# Breakout_carrier_bittern.net
KiCad netlist of a schematic drawn in EAGLE
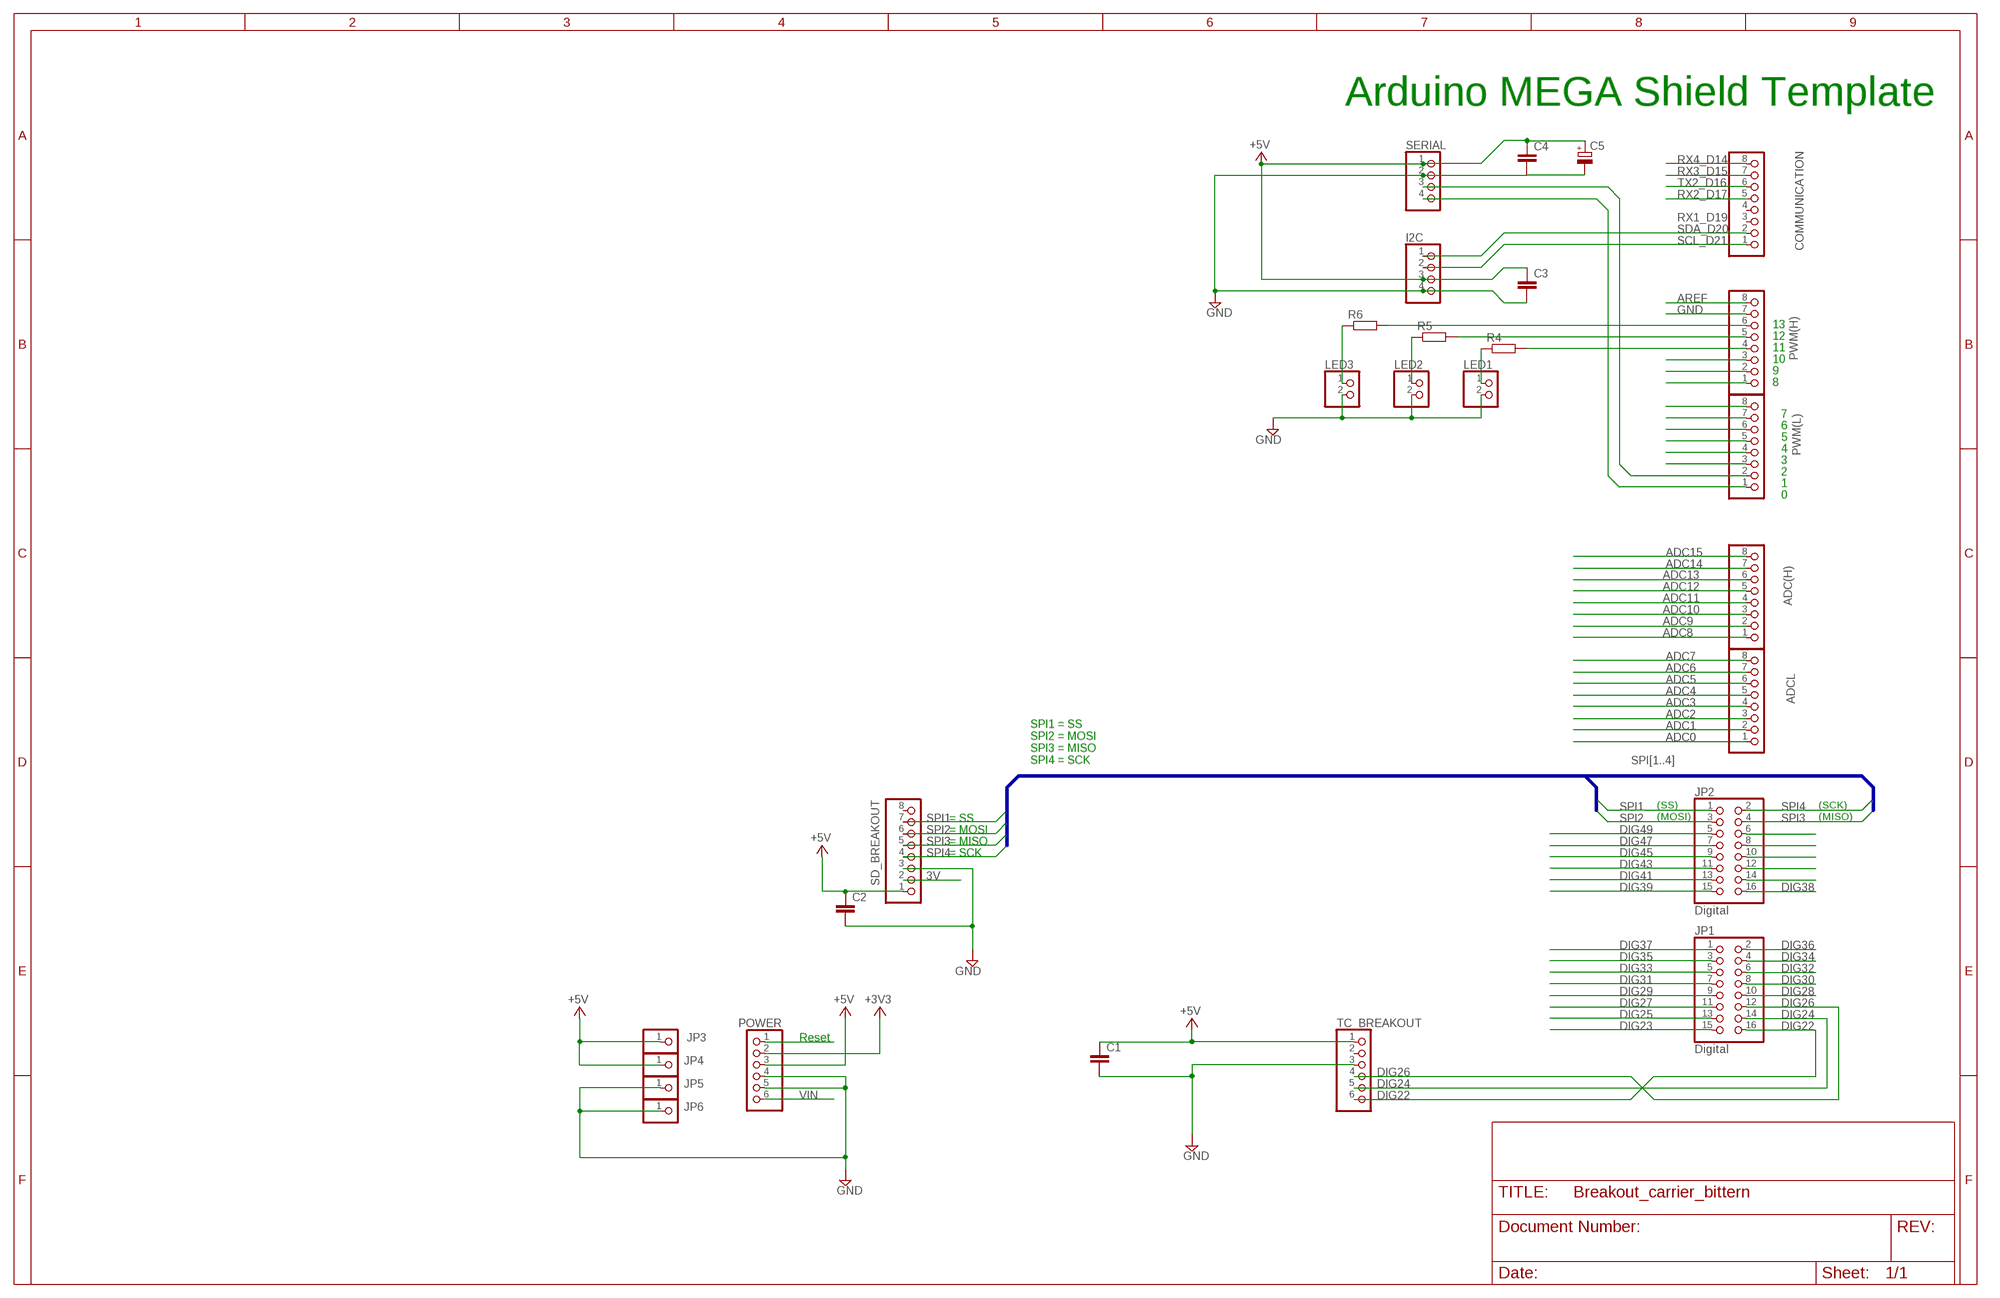
[diagram p0: schematic, sheet 1]

(export (version "E")
  (design (tool "Eeschema 10.0.6"))
  (components
    (comp (ref "ADC(H)")
      (value "PINHD-1X8")
      (footprint "eagle-import:1X08")
      (libsource (lib "eagle-import") (part "PINHD-1X8"))
    )
    (comp (ref "ADCL")
      (value "PINHD-1X8")
      (footprint "eagle-import:1X08")
      (libsource (lib "eagle-import") (part "PINHD-1X8"))
    )
    (comp (ref "C1")
      (value "C-EU050-045X075")
      (footprint "eagle-import:C050-045X075")
      (libsource (lib "eagle-import") (part "C-EU050-045X075"))
    )
    (comp (ref "C2")
      (value "C-EU050-045X075")
      (footprint "eagle-import:C050-045X075")
      (libsource (lib "eagle-import") (part "C-EU050-045X075"))
    )
    (comp (ref "C3")
      (value "C-EU050-045X075")
      (footprint "eagle-import:C050-045X075")
      (libsource (lib "eagle-import") (part "C-EU050-045X075"))
    )
    (comp (ref "C4")
      (value "C-EU050-045X075")
      (footprint "eagle-import:C050-045X075")
      (libsource (lib "eagle-import") (part "C-EU050-045X075"))
    )
    (comp (ref "C5")
      (value "CPOL-EUE2.5-6")
      (footprint "eagle-import:E2,5-6")
      (libsource (lib "eagle-import") (part "CPOL-EUE2.5-6"))
    )
    (comp (ref "COMMUNICATION")
      (value "PINHD-1X8")
      (footprint "eagle-import:1X08")
      (libsource (lib "eagle-import") (part "PINHD-1X8"))
    )
    (comp (ref "I2C")
      (value "PINHD-1X4")
      (footprint "eagle-import:1X04")
      (libsource (lib "eagle-import") (part "PINHD-1X4"))
    )
    (comp (ref "JP1")
      (value "Digital")
      (footprint "eagle-import:2X08")
      (libsource (lib "eagle-import") (part "PINHD-2X8"))
    )
    (comp (ref "JP2")
      (value "Digital")
      (footprint "eagle-import:2X08")
      (libsource (lib "eagle-import") (part "PINHD-2X8"))
    )
    (comp (ref "JP3")
      (value "PINHD-1X1")
      (footprint "eagle-import:1X01")
      (libsource (lib "eagle-import") (part "PINHD-1X1"))
    )
    (comp (ref "JP4")
      (value "PINHD-1X1")
      (footprint "eagle-import:1X01")
      (libsource (lib "eagle-import") (part "PINHD-1X1"))
    )
    (comp (ref "JP5")
      (value "PINHD-1X1")
      (footprint "eagle-import:1X01")
      (libsource (lib "eagle-import") (part "PINHD-1X1"))
    )
    (comp (ref "JP6")
      (value "PINHD-1X1")
      (footprint "eagle-import:1X01")
      (libsource (lib "eagle-import") (part "PINHD-1X1"))
    )
    (comp (ref "LED1")
      (value "PINHD-1X2")
      (footprint "eagle-import:1X02")
      (libsource (lib "eagle-import") (part "PINHD-1X2"))
    )
    (comp (ref "LED2")
      (value "PINHD-1X2")
      (footprint "eagle-import:1X02")
      (libsource (lib "eagle-import") (part "PINHD-1X2"))
    )
    (comp (ref "LED3")
      (value "PINHD-1X2")
      (footprint "eagle-import:1X02")
      (libsource (lib "eagle-import") (part "PINHD-1X2"))
    )
    (comp (ref "POWER")
      (value "PINHD-1X6")
      (footprint "eagle-import:1X06")
      (libsource (lib "eagle-import") (part "PINHD-1X6"))
    )
    (comp (ref "PWM(H)")
      (value "PINHD-1X8")
      (footprint "eagle-import:1X08")
      (libsource (lib "eagle-import") (part "PINHD-1X8"))
    )
    (comp (ref "PWM(L)")
      (value "PINHD-1X8")
      (footprint "eagle-import:1X08")
      (libsource (lib "eagle-import") (part "PINHD-1X8"))
    )
    (comp (ref "R4")
      (value "R-EU_0309/12")
      (footprint "eagle-import:0309_12")
      (libsource (lib "eagle-import") (part "R-EU_0309/12"))
    )
    (comp (ref "R5")
      (value "R-EU_0309/12")
      (footprint "eagle-import:0309_12")
      (libsource (lib "eagle-import") (part "R-EU_0309/12"))
    )
    (comp (ref "R6")
      (value "R-EU_0309/12")
      (footprint "eagle-import:0309_12")
      (libsource (lib "eagle-import") (part "R-EU_0309/12"))
    )
    (comp (ref "SD_BREAKOUT")
      (value "PINHD-1X8")
      (footprint "eagle-import:1X08")
      (libsource (lib "eagle-import") (part "PINHD-1X8"))
    )
    (comp (ref "SERIAL")
      (value "PINHD-1X4")
      (footprint "eagle-import:1X04")
      (libsource (lib "eagle-import") (part "PINHD-1X4"))
    )
    (comp (ref "TC_BREAKOUT")
      (value "PINHD-1X6")
      (footprint "eagle-import:1X06")
      (libsource (lib "eagle-import") (part "PINHD-1X6"))
    )
  )
  (nets
    (net (code "1") (name "+3V3") (class "Default")
      (node (ref "POWER") (pin "2") (pinfunction "2_2") (pintype "passive"))
    )
    (net (code "2") (name "+5V") (class "Default")
      (node (ref "C1") (pin "1") (pinfunction "1_1") (pintype "passive"))
      (node (ref "C2") (pin "1") (pinfunction "1_1") (pintype "passive"))
      (node (ref "C3") (pin "1") (pinfunction "1_1") (pintype "passive"))
      (node (ref "C4") (pin "1") (pinfunction "1_1") (pintype "passive"))
      (node (ref "C5") (pin "+") (pinfunction "+_+") (pintype "passive"))
      (node (ref "I2C") (pin "3") (pinfunction "3_3") (pintype "passive"))
      (node (ref "JP3") (pin "1") (pinfunction "1_1") (pintype "passive"))
      (node (ref "JP4") (pin "1") (pinfunction "1_1") (pintype "passive"))
      (node (ref "POWER") (pin "3") (pinfunction "3_3") (pintype "passive"))
      (node (ref "SD_BREAKOUT") (pin "1") (pinfunction "1_1") (pintype "passive"))
      (node (ref "SERIAL") (pin "1") (pinfunction "1_1") (pintype "passive"))
      (node (ref "TC_BREAKOUT") (pin "1") (pinfunction "1_1") (pintype "passive"))
    )
    (net (code "3") (name "/3V") (class "Default")
      (node (ref "SD_BREAKOUT") (pin "2") (pinfunction "2_2") (pintype "passive"))
    )
    (net (code "4") (name "/ADC0") (class "Default")
      (node (ref "ADCL") (pin "1") (pinfunction "1_1") (pintype "passive"))
    )
    (net (code "5") (name "/ADC1") (class "Default")
      (node (ref "ADCL") (pin "2") (pinfunction "2_2") (pintype "passive"))
    )
    (net (code "6") (name "/ADC2") (class "Default")
      (node (ref "ADCL") (pin "3") (pinfunction "3_3") (pintype "passive"))
    )
    (net (code "7") (name "/ADC3") (class "Default")
      (node (ref "ADCL") (pin "4") (pinfunction "4_4") (pintype "passive"))
    )
    (net (code "8") (name "/ADC4") (class "Default")
      (node (ref "ADCL") (pin "5") (pinfunction "5_5") (pintype "passive"))
    )
    (net (code "9") (name "/ADC5") (class "Default")
      (node (ref "ADCL") (pin "6") (pinfunction "6_6") (pintype "passive"))
    )
    (net (code "10") (name "/ADC6") (class "Default")
      (node (ref "ADCL") (pin "7") (pinfunction "7_7") (pintype "passive"))
    )
    (net (code "11") (name "/ADC7") (class "Default")
      (node (ref "ADCL") (pin "8") (pinfunction "8_8") (pintype "passive"))
    )
    (net (code "12") (name "/ADC8") (class "Default")
      (node (ref "ADC(H)") (pin "1") (pinfunction "1_1") (pintype "passive"))
    )
    (net (code "13") (name "/ADC9") (class "Default")
      (node (ref "ADC(H)") (pin "2") (pinfunction "2_2") (pintype "passive"))
    )
    (net (code "14") (name "/ADC10") (class "Default")
      (node (ref "ADC(H)") (pin "3") (pinfunction "3_3") (pintype "passive"))
    )
    (net (code "15") (name "/ADC11") (class "Default")
      (node (ref "ADC(H)") (pin "4") (pinfunction "4_4") (pintype "passive"))
    )
    (net (code "16") (name "/ADC12") (class "Default")
      (node (ref "ADC(H)") (pin "5") (pinfunction "5_5") (pintype "passive"))
    )
    (net (code "17") (name "/ADC13") (class "Default")
      (node (ref "ADC(H)") (pin "6") (pinfunction "6_6") (pintype "passive"))
    )
    (net (code "18") (name "/ADC14") (class "Default")
      (node (ref "ADC(H)") (pin "7") (pinfunction "7_7") (pintype "passive"))
    )
    (net (code "19") (name "/ADC15") (class "Default")
      (node (ref "ADC(H)") (pin "8") (pinfunction "8_8") (pintype "passive"))
    )
    (net (code "20") (name "/AREF") (class "Default")
      (node (ref "PWM(H)") (pin "8") (pinfunction "8_8") (pintype "passive"))
    )
    (net (code "21") (name "/DIG22") (class "Default")
      (node (ref "JP1") (pin "16") (pinfunction "16_16") (pintype "passive"))
      (node (ref "TC_BREAKOUT") (pin "6") (pinfunction "6_6") (pintype "passive"))
    )
    (net (code "22") (name "/DIG23") (class "Default")
      (node (ref "JP1") (pin "15") (pinfunction "15_15") (pintype "passive"))
    )
    (net (code "23") (name "/DIG24") (class "Default")
      (node (ref "JP1") (pin "14") (pinfunction "14_14") (pintype "passive"))
      (node (ref "TC_BREAKOUT") (pin "5") (pinfunction "5_5") (pintype "passive"))
    )
    (net (code "24") (name "/DIG25") (class "Default")
      (node (ref "JP1") (pin "13") (pinfunction "13_13") (pintype "passive"))
    )
    (net (code "25") (name "/DIG26") (class "Default")
      (node (ref "JP1") (pin "12") (pinfunction "12_12") (pintype "passive"))
      (node (ref "TC_BREAKOUT") (pin "4") (pinfunction "4_4") (pintype "passive"))
    )
    (net (code "26") (name "/DIG27") (class "Default")
      (node (ref "JP1") (pin "11") (pinfunction "11_11") (pintype "passive"))
    )
    (net (code "27") (name "/DIG28") (class "Default")
      (node (ref "JP1") (pin "10") (pinfunction "10_10") (pintype "passive"))
    )
    (net (code "28") (name "/DIG29") (class "Default")
      (node (ref "JP1") (pin "9") (pinfunction "9_9") (pintype "passive"))
    )
    (net (code "29") (name "/DIG30") (class "Default")
      (node (ref "JP1") (pin "8") (pinfunction "8_8") (pintype "passive"))
    )
    (net (code "30") (name "/DIG31") (class "Default")
      (node (ref "JP1") (pin "7") (pinfunction "7_7") (pintype "passive"))
    )
    (net (code "31") (name "/DIG32") (class "Default")
      (node (ref "JP1") (pin "6") (pinfunction "6_6") (pintype "passive"))
    )
    (net (code "32") (name "/DIG33") (class "Default")
      (node (ref "JP1") (pin "5") (pinfunction "5_5") (pintype "passive"))
    )
    (net (code "33") (name "/DIG34") (class "Default")
      (node (ref "JP1") (pin "4") (pinfunction "4_4") (pintype "passive"))
    )
    (net (code "34") (name "/DIG35") (class "Default")
      (node (ref "JP1") (pin "3") (pinfunction "3_3") (pintype "passive"))
    )
    (net (code "35") (name "/DIG36") (class "Default")
      (node (ref "JP1") (pin "2") (pinfunction "2_2") (pintype "passive"))
    )
    (net (code "36") (name "/DIG37") (class "Default")
      (node (ref "JP1") (pin "1") (pinfunction "1_1") (pintype "passive"))
    )
    (net (code "37") (name "/DIG38") (class "Default")
      (node (ref "JP2") (pin "16") (pinfunction "16_16") (pintype "passive"))
    )
    (net (code "38") (name "/DIG39") (class "Default")
      (node (ref "JP2") (pin "15") (pinfunction "15_15") (pintype "passive"))
    )
    (net (code "39") (name "/DIG41") (class "Default")
      (node (ref "JP2") (pin "13") (pinfunction "13_13") (pintype "passive"))
    )
    (net (code "40") (name "/DIG43") (class "Default")
      (node (ref "JP2") (pin "11") (pinfunction "11_11") (pintype "passive"))
    )
    (net (code "41") (name "/DIG45") (class "Default")
      (node (ref "JP2") (pin "9") (pinfunction "9_9") (pintype "passive"))
    )
    (net (code "42") (name "/DIG47") (class "Default")
      (node (ref "JP2") (pin "7") (pinfunction "7_7") (pintype "passive"))
    )
    (net (code "43") (name "/DIG49") (class "Default")
      (node (ref "JP2") (pin "5") (pinfunction "5_5") (pintype "passive"))
    )
    (net (code "44") (name "/RX1_D19") (class "Default")
      (node (ref "PWM(L)") (pin "1") (pinfunction "1_1") (pintype "passive"))
      (node (ref "SERIAL") (pin "4") (pinfunction "4_4") (pintype "passive"))
    )
    (net (code "45") (name "/RX2_D17") (class "Default")
      (node (ref "COMMUNICATION") (pin "5") (pinfunction "5_5") (pintype "passive"))
    )
    (net (code "46") (name "/RX3_D15") (class "Default")
      (node (ref "COMMUNICATION") (pin "7") (pinfunction "7_7") (pintype "passive"))
    )
    (net (code "47") (name "/RX4_D14") (class "Default")
      (node (ref "COMMUNICATION") (pin "8") (pinfunction "8_8") (pintype "passive"))
    )
    (net (code "48") (name "/SCL_D21") (class "Default")
      (node (ref "COMMUNICATION") (pin "1") (pinfunction "1_1") (pintype "passive"))
      (node (ref "I2C") (pin "2") (pinfunction "2_2") (pintype "passive"))
    )
    (net (code "49") (name "/SDA_D20") (class "Default")
      (node (ref "COMMUNICATION") (pin "2") (pinfunction "2_2") (pintype "passive"))
      (node (ref "I2C") (pin "1") (pinfunction "1_1") (pintype "passive"))
    )
    (net (code "50") (name "/SPI1") (class "Default")
      (node (ref "JP2") (pin "1") (pinfunction "1_1") (pintype "passive"))
      (node (ref "SD_BREAKOUT") (pin "7") (pinfunction "7_7") (pintype "passive"))
    )
    (net (code "51") (name "/SPI2") (class "Default")
      (node (ref "JP2") (pin "3") (pinfunction "3_3") (pintype "passive"))
      (node (ref "SD_BREAKOUT") (pin "6") (pinfunction "6_6") (pintype "passive"))
    )
    (net (code "52") (name "/SPI3") (class "Default")
      (node (ref "JP2") (pin "4") (pinfunction "4_4") (pintype "passive"))
      (node (ref "SD_BREAKOUT") (pin "5") (pinfunction "5_5") (pintype "passive"))
    )
    (net (code "53") (name "/SPI4") (class "Default")
      (node (ref "JP2") (pin "2") (pinfunction "2_2") (pintype "passive"))
      (node (ref "SD_BREAKOUT") (pin "4") (pinfunction "4_4") (pintype "passive"))
    )
    (net (code "55") (name "/TX2_D16") (class "Default")
      (node (ref "COMMUNICATION") (pin "6") (pinfunction "6_6") (pintype "passive"))
    )
    (net (code "56") (name "/VIN") (class "Default")
      (node (ref "POWER") (pin "6") (pinfunction "6_6") (pintype "passive"))
    )
    (net (code "57") (name "GND") (class "Default")
      (node (ref "C1") (pin "2") (pinfunction "2_2") (pintype "passive"))
      (node (ref "C2") (pin "2") (pinfunction "2_2") (pintype "passive"))
      (node (ref "C3") (pin "2") (pinfunction "2_2") (pintype "passive"))
      (node (ref "C4") (pin "2") (pinfunction "2_2") (pintype "passive"))
      (node (ref "C5") (pin "-") (pinfunction "-_-") (pintype "passive"))
      (node (ref "I2C") (pin "4") (pinfunction "4_4") (pintype "passive"))
      (node (ref "JP5") (pin "1") (pinfunction "1_1") (pintype "passive"))
      (node (ref "JP6") (pin "1") (pinfunction "1_1") (pintype "passive"))
      (node (ref "LED1") (pin "2") (pinfunction "2_2") (pintype "passive"))
      (node (ref "LED2") (pin "2") (pinfunction "2_2") (pintype "passive"))
      (node (ref "LED3") (pin "2") (pinfunction "2_2") (pintype "passive"))
      (node (ref "POWER") (pin "4") (pinfunction "4_4") (pintype "passive"))
      (node (ref "POWER") (pin "5") (pinfunction "5_5") (pintype "passive"))
      (node (ref "PWM(H)") (pin "7") (pinfunction "7_7") (pintype "passive"))
      (node (ref "SD_BREAKOUT") (pin "3") (pinfunction "3_3") (pintype "passive"))
      (node (ref "SERIAL") (pin "2") (pinfunction "2_2") (pintype "passive"))
      (node (ref "TC_BREAKOUT") (pin "3") (pinfunction "3_3") (pintype "passive"))
    )
    (net (code "58") (name "Net-(LED1-Pad1)") (class "Default")
      (node (ref "LED1") (pin "1") (pinfunction "1_1") (pintype "passive"))
      (node (ref "R4") (pin "1") (pinfunction "1_1") (pintype "passive"))
    )
    (net (code "59") (name "Net-(LED2-Pad1)") (class "Default")
      (node (ref "LED2") (pin "1") (pinfunction "1_1") (pintype "passive"))
      (node (ref "R5") (pin "1") (pinfunction "1_1") (pintype "passive"))
    )
    (net (code "60") (name "Net-(LED3-Pad1)") (class "Default")
      (node (ref "LED3") (pin "1") (pinfunction "1_1") (pintype "passive"))
      (node (ref "R6") (pin "1") (pinfunction "1_1") (pintype "passive"))
    )
    (net (code "61") (name "Net-(PWM(H)-Pad4)") (class "Default")
      (node (ref "PWM(H)") (pin "4") (pinfunction "4_4") (pintype "passive"))
      (node (ref "R4") (pin "2") (pinfunction "2_2") (pintype "passive"))
    )
    (net (code "62") (name "Net-(PWM(H)-Pad5)") (class "Default")
      (node (ref "PWM(H)") (pin "5") (pinfunction "5_5") (pintype "passive"))
      (node (ref "R5") (pin "2") (pinfunction "2_2") (pintype "passive"))
    )
    (net (code "63") (name "Net-(PWM(H)-Pad6)") (class "Default")
      (node (ref "PWM(H)") (pin "6") (pinfunction "6_6") (pintype "passive"))
      (node (ref "R6") (pin "2") (pinfunction "2_2") (pintype "passive"))
    )
    (net (code "64") (name "Net-(PWM(L)-Pad2)") (class "Default")
      (node (ref "PWM(L)") (pin "2") (pinfunction "2_2") (pintype "passive"))
      (node (ref "SERIAL") (pin "3") (pinfunction "3_3") (pintype "passive"))
    )
    (net (code "65") (name "unconnected-(COMMUNICATION-Pad3)") (class "Default")
      (node (ref "COMMUNICATION") (pin "3") (pinfunction "3_3") (pintype "passive"))
    )
    (net (code "66") (name "unconnected-(COMMUNICATION-Pad4)") (class "Default")
      (node (ref "COMMUNICATION") (pin "4") (pinfunction "4_4") (pintype "passive"))
    )
    (net (code "67") (name "unconnected-(JP2-Pad6)") (class "Default")
      (node (ref "JP2") (pin "6") (pinfunction "6_6") (pintype "passive"))
    )
    (net (code "68") (name "unconnected-(JP2-Pad8)") (class "Default")
      (node (ref "JP2") (pin "8") (pinfunction "8_8") (pintype "passive"))
    )
    (net (code "69") (name "unconnected-(JP2-Pad10)") (class "Default")
      (node (ref "JP2") (pin "10") (pinfunction "10_10") (pintype "passive"))
    )
    (net (code "70") (name "unconnected-(JP2-Pad12)") (class "Default")
      (node (ref "JP2") (pin "12") (pinfunction "12_12") (pintype "passive"))
    )
    (net (code "71") (name "unconnected-(JP2-Pad14)") (class "Default")
      (node (ref "JP2") (pin "14") (pinfunction "14_14") (pintype "passive"))
    )
    (net (code "72") (name "unconnected-(POWER-Pad1)") (class "Default")
      (node (ref "POWER") (pin "1") (pinfunction "1_1") (pintype "passive"))
    )
    (net (code "73") (name "unconnected-(PWM(H)-Pad1)") (class "Default")
      (node (ref "PWM(H)") (pin "1") (pinfunction "1_1") (pintype "passive"))
    )
    (net (code "74") (name "unconnected-(PWM(H)-Pad2)") (class "Default")
      (node (ref "PWM(H)") (pin "2") (pinfunction "2_2") (pintype "passive"))
    )
    (net (code "75") (name "unconnected-(PWM(H)-Pad3)") (class "Default")
      (node (ref "PWM(H)") (pin "3") (pinfunction "3_3") (pintype "passive"))
    )
    (net (code "76") (name "unconnected-(PWM(L)-Pad3)") (class "Default")
      (node (ref "PWM(L)") (pin "3") (pinfunction "3_3") (pintype "passive"))
    )
    (net (code "77") (name "unconnected-(PWM(L)-Pad4)") (class "Default")
      (node (ref "PWM(L)") (pin "4") (pinfunction "4_4") (pintype "passive"))
    )
    (net (code "78") (name "unconnected-(PWM(L)-Pad5)") (class "Default")
      (node (ref "PWM(L)") (pin "5") (pinfunction "5_5") (pintype "passive"))
    )
    (net (code "79") (name "unconnected-(PWM(L)-Pad6)") (class "Default")
      (node (ref "PWM(L)") (pin "6") (pinfunction "6_6") (pintype "passive"))
    )
    (net (code "80") (name "unconnected-(PWM(L)-Pad7)") (class "Default")
      (node (ref "PWM(L)") (pin "7") (pinfunction "7_7") (pintype "passive"))
    )
    (net (code "81") (name "unconnected-(PWM(L)-Pad8)") (class "Default")
      (node (ref "PWM(L)") (pin "8") (pinfunction "8_8") (pintype "passive"))
    )
    (net (code "82") (name "unconnected-(SD_BREAKOUT-Pad8)") (class "Default")
      (node (ref "SD_BREAKOUT") (pin "8") (pinfunction "8_8") (pintype "passive"))
    )
    (net (code "83") (name "unconnected-(TC_BREAKOUT-Pad2)") (class "Default")
      (node (ref "TC_BREAKOUT") (pin "2") (pinfunction "2_2") (pintype "passive"))
    )
  )
)
